# CX4_enable_logic.net
KiCad netlist of a schematic drawn in Altium Designer
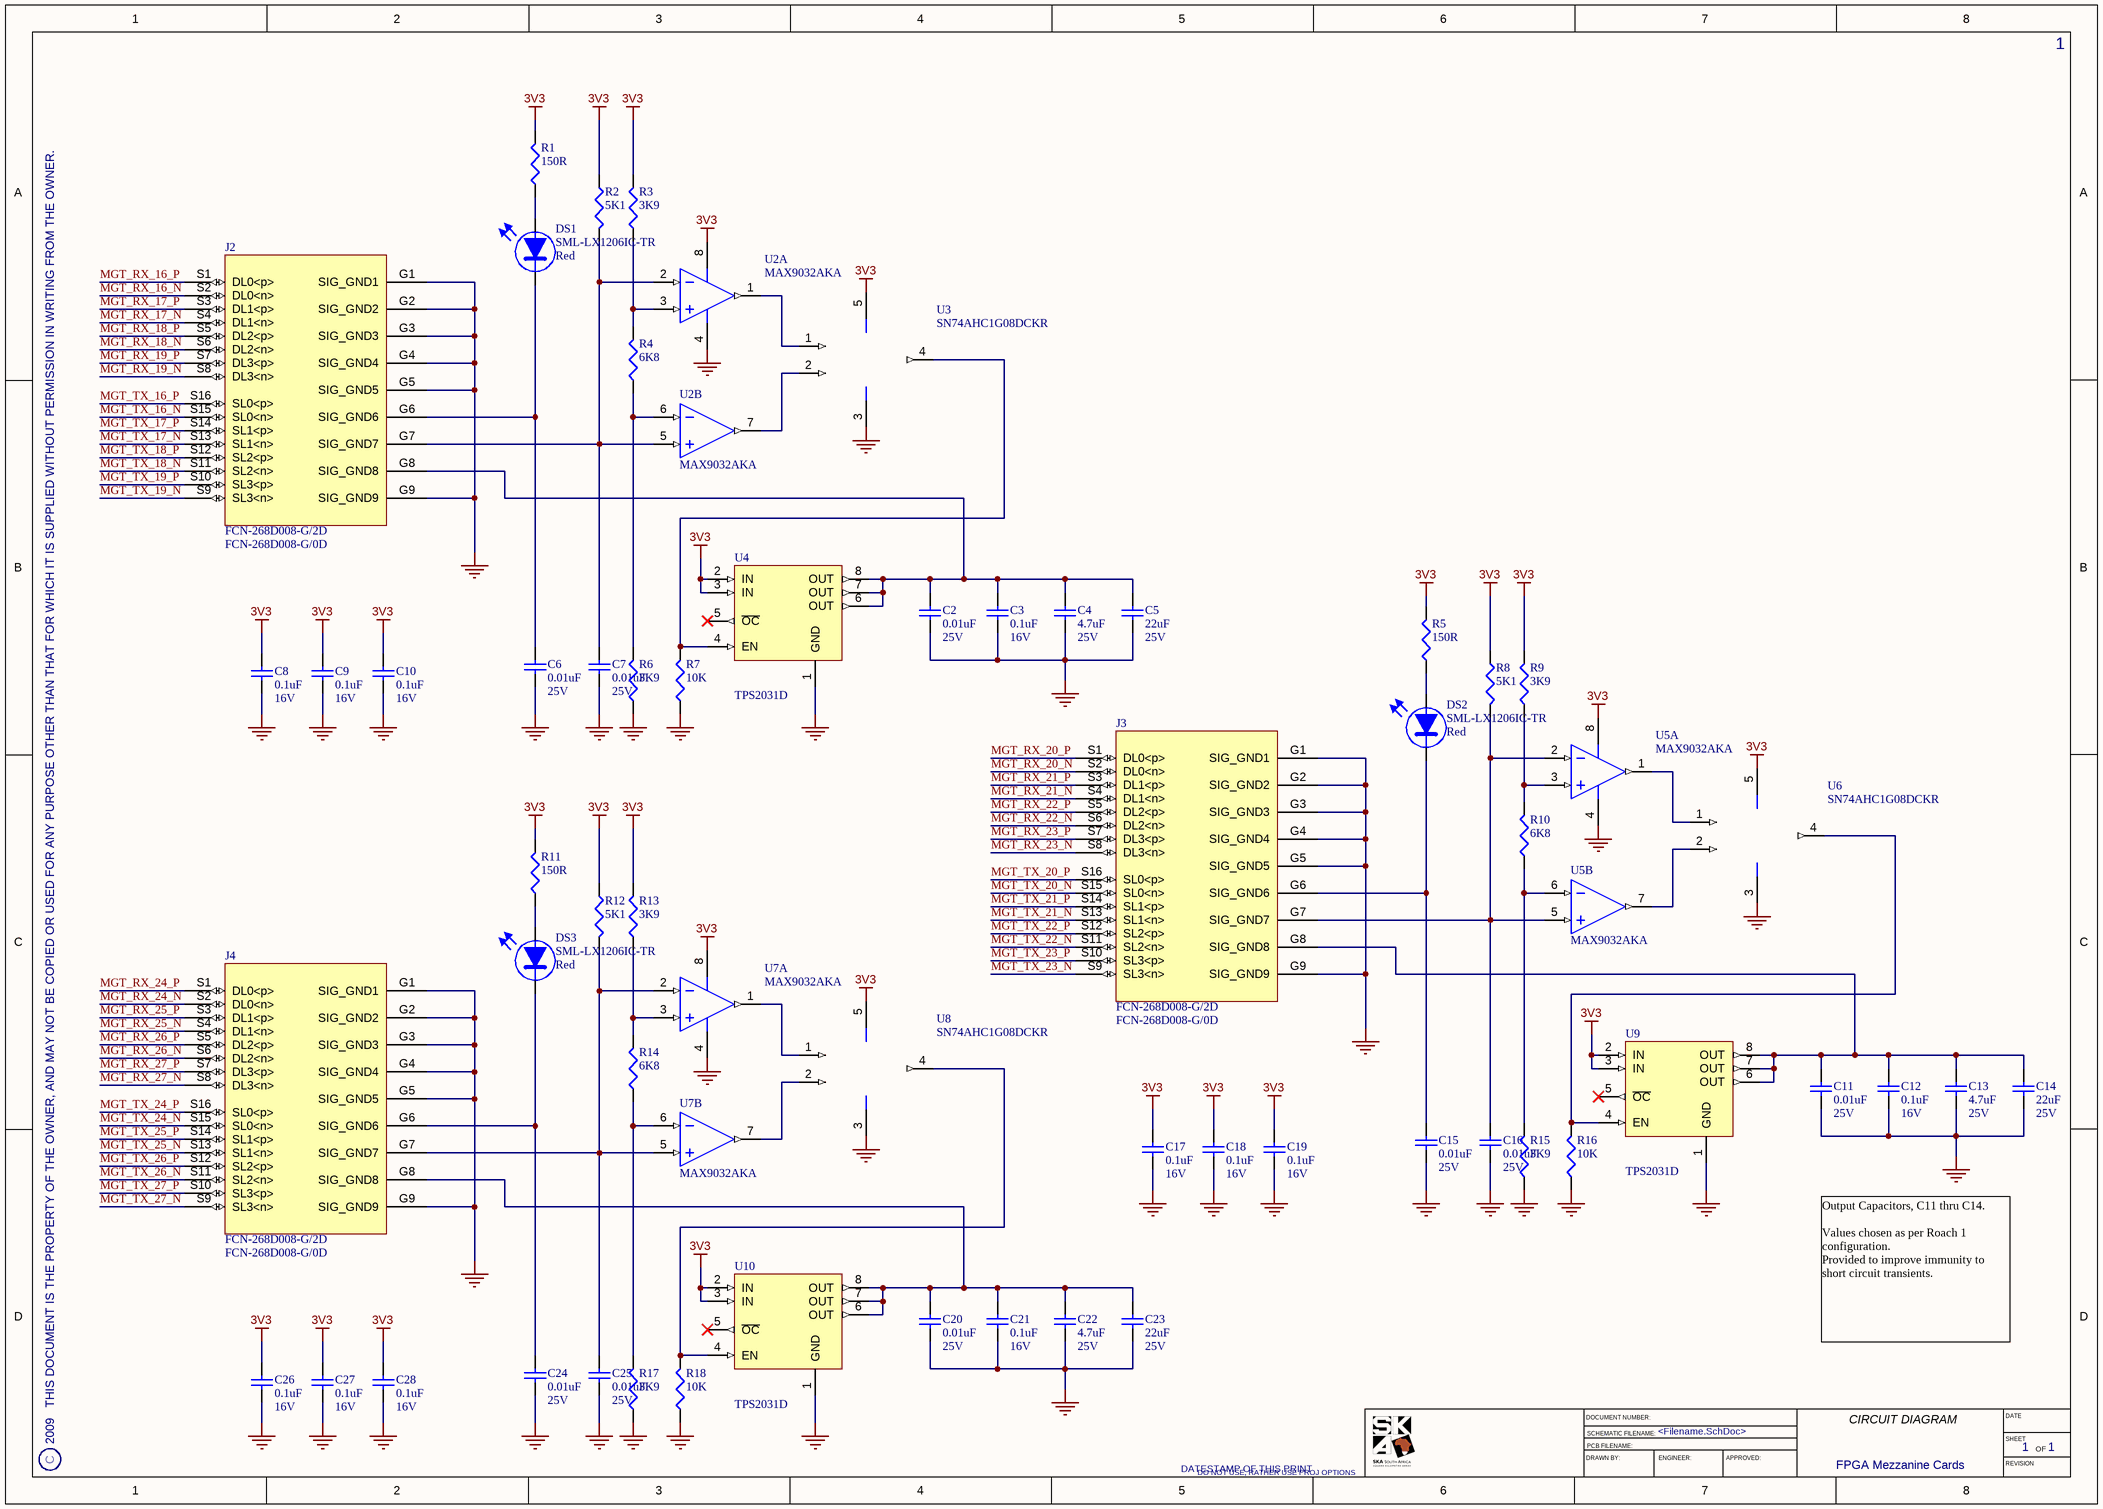
[diagram p0: CX4_enable_logic.SchDoc]

(export (version "E")
  (design (tool "Eeschema 10.0.6"))
  (components
    (comp (ref "C2")
      (value "0.01uF")
      (footprint "CAPC1005X55L")
      (description "0.01uF, Ceramic Capacitor")
      (fields
        (field (name "RATING") "25V")
        (field (name "MANUFACTURER") "MURATA")
        (field (name "PARTNUM") "GRM155R71E103KA01D")
      )
      (libsource (lib "altium_db") (part "CapStd"))
    )
    (comp (ref "C3")
      (value "0.1uF")
      (footprint "CAPC1005X60L")
      (description "0.1uF, Ceramic Capacitor")
      (fields
        (field (name "RATING") "16V")
        (field (name "MANUFACTURER") "VENKEL")
        (field (name "PARTNUM") "C0402X7R160-104KN")
      )
      (libsource (lib "altium_db") (part "CapStd"))
    )
    (comp (ref "C4")
      (value "4.7uF")
      (footprint "CAPC2012X127L")
      (description "4.7uF, Ceramic Capacitor")
      (fields
        (field (name "RATING") "25V")
        (field (name "MANUFACTURER") "MURATA")
        (field (name "PARTNUM") "GRM21BR61E475KA12K")
      )
      (libsource (lib "altium_db") (part "CapStd"))
    )
    (comp (ref "C5")
      (value "22uF")
      (footprint "CAPC3225X270L")
      (description "22uF, Ceramic Capacitor")
      (fields
        (field (name "RATING") "25V")
        (field (name "MANUFACTURER") "MURATA")
        (field (name "PARTNUM") "GRM32ER61E226ME15L")
      )
      (libsource (lib "altium_db") (part "CapStd"))
    )
    (comp (ref "C6")
      (value "0.01uF")
      (footprint "CAPC1005X55L")
      (description "0.01uF, Ceramic Capacitor")
      (fields
        (field (name "RATING") "25V")
        (field (name "MANUFACTURER") "MURATA")
        (field (name "PARTNUM") "GRM155R71E103KA01D")
      )
      (libsource (lib "altium_db") (part "CapStd"))
    )
    (comp (ref "C7")
      (value "0.01uF")
      (footprint "CAPC1005X55L")
      (description "0.01uF, Ceramic Capacitor")
      (fields
        (field (name "RATING") "25V")
        (field (name "MANUFACTURER") "MURATA")
        (field (name "PARTNUM") "GRM155R71E103KA01D")
      )
      (libsource (lib "altium_db") (part "CapStd"))
    )
    (comp (ref "C8")
      (value "0.1uF")
      (footprint "CAPC1005X60L")
      (description "0.1uF, Ceramic Capacitor")
      (fields
        (field (name "RATING") "16V")
        (field (name "MANUFACTURER") "VENKEL")
        (field (name "PARTNUM") "C0402X7R160-104KN")
      )
      (libsource (lib "altium_db") (part "CapStd"))
    )
    (comp (ref "C9")
      (value "0.1uF")
      (footprint "CAPC1005X60L")
      (description "0.1uF, Ceramic Capacitor")
      (fields
        (field (name "RATING") "16V")
        (field (name "MANUFACTURER") "VENKEL")
        (field (name "PARTNUM") "C0402X7R160-104KN")
      )
      (libsource (lib "altium_db") (part "CapStd"))
    )
    (comp (ref "C10")
      (value "0.1uF")
      (footprint "CAPC1005X60L")
      (description "0.1uF, Ceramic Capacitor")
      (fields
        (field (name "RATING") "16V")
        (field (name "MANUFACTURER") "VENKEL")
        (field (name "PARTNUM") "C0402X7R160-104KN")
      )
      (libsource (lib "altium_db") (part "CapStd"))
    )
    (comp (ref "C11")
      (value "0.01uF")
      (footprint "CAPC1005X55L")
      (description "0.01uF, Ceramic Capacitor")
      (fields
        (field (name "RATING") "25V")
        (field (name "MANUFACTURER") "MURATA")
        (field (name "PARTNUM") "GRM155R71E103KA01D")
      )
      (libsource (lib "altium_db") (part "CapStd"))
    )
    (comp (ref "C12")
      (value "0.1uF")
      (footprint "CAPC1005X60L")
      (description "0.1uF, Ceramic Capacitor")
      (fields
        (field (name "RATING") "16V")
        (field (name "MANUFACTURER") "VENKEL")
        (field (name "PARTNUM") "C0402X7R160-104KN")
      )
      (libsource (lib "altium_db") (part "CapStd"))
    )
    (comp (ref "C13")
      (value "4.7uF")
      (footprint "CAPC2012X127L")
      (description "4.7uF, Ceramic Capacitor")
      (fields
        (field (name "RATING") "25V")
        (field (name "MANUFACTURER") "MURATA")
        (field (name "PARTNUM") "GRM21BR61E475KA12K")
      )
      (libsource (lib "altium_db") (part "CapStd"))
    )
    (comp (ref "C14")
      (value "22uF")
      (footprint "CAPC3225X270L")
      (description "22uF, Ceramic Capacitor")
      (fields
        (field (name "RATING") "25V")
        (field (name "MANUFACTURER") "MURATA")
        (field (name "PARTNUM") "GRM32ER61E226ME15L")
      )
      (libsource (lib "altium_db") (part "CapStd"))
    )
    (comp (ref "C15")
      (value "0.01uF")
      (footprint "CAPC1005X55L")
      (description "0.01uF, Ceramic Capacitor")
      (fields
        (field (name "RATING") "25V")
        (field (name "MANUFACTURER") "MURATA")
        (field (name "PARTNUM") "GRM155R71E103KA01D")
      )
      (libsource (lib "altium_db") (part "CapStd"))
    )
    (comp (ref "C16")
      (value "0.01uF")
      (footprint "CAPC1005X55L")
      (description "0.01uF, Ceramic Capacitor")
      (fields
        (field (name "RATING") "25V")
        (field (name "MANUFACTURER") "MURATA")
        (field (name "PARTNUM") "GRM155R71E103KA01D")
      )
      (libsource (lib "altium_db") (part "CapStd"))
    )
    (comp (ref "C17")
      (value "0.1uF")
      (footprint "CAPC1005X60L")
      (description "0.1uF, Ceramic Capacitor")
      (fields
        (field (name "RATING") "16V")
        (field (name "MANUFACTURER") "VENKEL")
        (field (name "PARTNUM") "C0402X7R160-104KN")
      )
      (libsource (lib "altium_db") (part "CapStd"))
    )
    (comp (ref "C18")
      (value "0.1uF")
      (footprint "CAPC1005X60L")
      (description "0.1uF, Ceramic Capacitor")
      (fields
        (field (name "RATING") "16V")
        (field (name "MANUFACTURER") "VENKEL")
        (field (name "PARTNUM") "C0402X7R160-104KN")
      )
      (libsource (lib "altium_db") (part "CapStd"))
    )
    (comp (ref "C19")
      (value "0.1uF")
      (footprint "CAPC1005X60L")
      (description "0.1uF, Ceramic Capacitor")
      (fields
        (field (name "RATING") "16V")
        (field (name "MANUFACTURER") "VENKEL")
        (field (name "PARTNUM") "C0402X7R160-104KN")
      )
      (libsource (lib "altium_db") (part "CapStd"))
    )
    (comp (ref "C20")
      (value "0.01uF")
      (footprint "CAPC1005X55L")
      (description "0.01uF, Ceramic Capacitor")
      (fields
        (field (name "RATING") "25V")
        (field (name "MANUFACTURER") "MURATA")
        (field (name "PARTNUM") "GRM155R71E103KA01D")
      )
      (libsource (lib "altium_db") (part "CapStd"))
    )
    (comp (ref "C21")
      (value "0.1uF")
      (footprint "CAPC1005X60L")
      (description "0.1uF, Ceramic Capacitor")
      (fields
        (field (name "RATING") "16V")
        (field (name "MANUFACTURER") "VENKEL")
        (field (name "PARTNUM") "C0402X7R160-104KN")
      )
      (libsource (lib "altium_db") (part "CapStd"))
    )
    (comp (ref "C22")
      (value "4.7uF")
      (footprint "CAPC2012X127L")
      (description "4.7uF, Ceramic Capacitor")
      (fields
        (field (name "RATING") "25V")
        (field (name "MANUFACTURER") "MURATA")
        (field (name "PARTNUM") "GRM21BR61E475KA12K")
      )
      (libsource (lib "altium_db") (part "CapStd"))
    )
    (comp (ref "C23")
      (value "22uF")
      (footprint "CAPC3225X270L")
      (description "22uF, Ceramic Capacitor")
      (fields
        (field (name "RATING") "25V")
        (field (name "MANUFACTURER") "MURATA")
        (field (name "PARTNUM") "GRM32ER61E226ME15L")
      )
      (libsource (lib "altium_db") (part "CapStd"))
    )
    (comp (ref "C24")
      (value "0.01uF")
      (footprint "CAPC1005X55L")
      (description "0.01uF, Ceramic Capacitor")
      (fields
        (field (name "RATING") "25V")
        (field (name "MANUFACTURER") "MURATA")
        (field (name "PARTNUM") "GRM155R71E103KA01D")
      )
      (libsource (lib "altium_db") (part "CapStd"))
    )
    (comp (ref "C25")
      (value "0.01uF")
      (footprint "CAPC1005X55L")
      (description "0.01uF, Ceramic Capacitor")
      (fields
        (field (name "RATING") "25V")
        (field (name "MANUFACTURER") "MURATA")
        (field (name "PARTNUM") "GRM155R71E103KA01D")
      )
      (libsource (lib "altium_db") (part "CapStd"))
    )
    (comp (ref "C26")
      (value "0.1uF")
      (footprint "CAPC1005X60L")
      (description "0.1uF, Ceramic Capacitor")
      (fields
        (field (name "RATING") "16V")
        (field (name "MANUFACTURER") "VENKEL")
        (field (name "PARTNUM") "C0402X7R160-104KN")
      )
      (libsource (lib "altium_db") (part "CapStd"))
    )
    (comp (ref "C27")
      (value "0.1uF")
      (footprint "CAPC1005X60L")
      (description "0.1uF, Ceramic Capacitor")
      (fields
        (field (name "RATING") "16V")
        (field (name "MANUFACTURER") "VENKEL")
        (field (name "PARTNUM") "C0402X7R160-104KN")
      )
      (libsource (lib "altium_db") (part "CapStd"))
    )
    (comp (ref "C28")
      (value "0.1uF")
      (footprint "CAPC1005X60L")
      (description "0.1uF, Ceramic Capacitor")
      (fields
        (field (name "RATING") "16V")
        (field (name "MANUFACTURER") "VENKEL")
        (field (name "PARTNUM") "C0402X7R160-104KN")
      )
      (libsource (lib "altium_db") (part "CapStd"))
    )
    (comp (ref "DS1")
      (value "SML-LX1206IC-TR")
      (footprint "LEDC3216X120N")
      (description "Red, Surface mount, LED, 1206")
      (fields (field (name "COLOUR") "Red") (field (name "MANUFACTURER") "LUMEX"))
      (libsource (lib "altium_db") (part "LEDSTD"))
    )
    (comp (ref "DS2")
      (value "SML-LX1206IC-TR")
      (footprint "LEDC3216X120N")
      (description "Red, Surface mount, LED, 1206")
      (fields (field (name "COLOUR") "Red") (field (name "MANUFACTURER") "LUMEX"))
      (libsource (lib "altium_db") (part "LEDSTD"))
    )
    (comp (ref "DS3")
      (value "SML-LX1206IC-TR")
      (footprint "LEDC3216X120N")
      (description "Red, Surface mount, LED, 1206")
      (fields (field (name "COLOUR") "Red") (field (name "MANUFACTURER") "LUMEX"))
      (libsource (lib "altium_db") (part "LEDSTD"))
    )
    (comp (ref "J2")
      (value "FCN-268D008-G/2D")
      (footprint "FCN-268D008-G")
      (description "CX4/Infiniband 4 channel Socket Connector")
      (fields (field (name "PARTNUM") "FCN-268D008-G/0D") (field (name "MANUFACTURER") "Fujitsu"))
      (libsource (lib "altium_db") (part "FCN-268D008-G_2"))
    )
    (comp (ref "J3")
      (value "FCN-268D008-G/2D")
      (footprint "FCN-268D008-G")
      (description "CX4/Infiniband 4 channel Socket Connector")
      (fields (field (name "PARTNUM") "FCN-268D008-G/0D") (field (name "MANUFACTURER") "Fujitsu"))
      (libsource (lib "altium_db") (part "FCN-268D008-G_2"))
    )
    (comp (ref "J4")
      (value "FCN-268D008-G/2D")
      (footprint "FCN-268D008-G")
      (description "CX4/Infiniband 4 channel Socket Connector")
      (fields (field (name "PARTNUM") "FCN-268D008-G/0D") (field (name "MANUFACTURER") "Fujitsu"))
      (libsource (lib "altium_db") (part "FCN-268D008-G_2"))
    )
    (comp (ref "R1")
      (value "150R")
      (footprint "RESC1005X40L")
      (description "150R, 1.1mm x 0.5mm, Thick Film Resistor")
      (fields (field (name "MANUFACTURER") "ROYALOHM") (field (name "PARTNUM") "0402WGJ0151T1E"))
      (libsource (lib "altium_db") (part "ResStd"))
    )
    (comp (ref "R2")
      (value "5K1")
      (footprint "RESC1005X40L")
      (description "5K1, 1.1mm x 0.5mm, Thick Film Resistor")
      (fields (field (name "MANUFACTURER") "ROYALOHM") (field (name "PARTNUM") "0402WAJ0512T1E"))
      (libsource (lib "altium_db") (part "ResStd"))
    )
    (comp (ref "R3")
      (value "3K9")
      (footprint "RESC1005X40L")
      (description "3K9, 1.1mm x 0.5mm, Thick Film Resistor")
      (fields (field (name "MANUFACTURER") "ROYALOHM") (field (name "PARTNUM") "0402WGJ0392T1E"))
      (libsource (lib "altium_db") (part "ResStd"))
    )
    (comp (ref "R4")
      (value "6K8")
      (footprint "RESC1005X40L")
      (description "6K8, 1.1mm x 0.5mm, Thick Film Resistor")
      (fields (field (name "MANUFACTURER") "ROYALOHM") (field (name "PARTNUM") "0402WGJ0682T1E"))
      (libsource (lib "altium_db") (part "ResStd"))
    )
    (comp (ref "R5")
      (value "150R")
      (footprint "RESC1005X40L")
      (description "150R, 1.1mm x 0.5mm, Thick Film Resistor")
      (fields (field (name "MANUFACTURER") "ROYALOHM") (field (name "PARTNUM") "0402WGJ0151T1E"))
      (libsource (lib "altium_db") (part "ResStd"))
    )
    (comp (ref "R6")
      (value "3K9")
      (footprint "RESC1005X40L")
      (description "3K9, 1.1mm x 0.5mm, Thick Film Resistor")
      (fields (field (name "MANUFACTURER") "ROYALOHM") (field (name "PARTNUM") "0402WGJ0392T1E"))
      (libsource (lib "altium_db") (part "ResStd"))
    )
    (comp (ref "R7")
      (value "10K")
      (footprint "RESC1005X40L")
      (description "10K, 1.1mm x 0.5mm, Thick Film Resistor")
      (fields (field (name "MANUFACTURER") "ROYALOHM") (field (name "PARTNUM") "0402WGJ0103T1E"))
      (libsource (lib "altium_db") (part "ResStd"))
    )
    (comp (ref "R8")
      (value "5K1")
      (footprint "RESC1005X40L")
      (description "5K1, 1.1mm x 0.5mm, Thick Film Resistor")
      (fields (field (name "MANUFACTURER") "ROYALOHM") (field (name "PARTNUM") "0402WAJ0512T1E"))
      (libsource (lib "altium_db") (part "ResStd"))
    )
    (comp (ref "R9")
      (value "3K9")
      (footprint "RESC1005X40L")
      (description "3K9, 1.1mm x 0.5mm, Thick Film Resistor")
      (fields (field (name "MANUFACTURER") "ROYALOHM") (field (name "PARTNUM") "0402WGJ0392T1E"))
      (libsource (lib "altium_db") (part "ResStd"))
    )
    (comp (ref "R10")
      (value "6K8")
      (footprint "RESC1005X40L")
      (description "6K8, 1.1mm x 0.5mm, Thick Film Resistor")
      (fields (field (name "MANUFACTURER") "ROYALOHM") (field (name "PARTNUM") "0402WGJ0682T1E"))
      (libsource (lib "altium_db") (part "ResStd"))
    )
    (comp (ref "R11")
      (value "150R")
      (footprint "RESC1005X40L")
      (description "150R, 1.1mm x 0.5mm, Thick Film Resistor")
      (fields (field (name "MANUFACTURER") "ROYALOHM") (field (name "PARTNUM") "0402WGJ0151T1E"))
      (libsource (lib "altium_db") (part "ResStd"))
    )
    (comp (ref "R12")
      (value "5K1")
      (footprint "RESC1005X40L")
      (description "5K1, 1.1mm x 0.5mm, Thick Film Resistor")
      (fields (field (name "MANUFACTURER") "ROYALOHM") (field (name "PARTNUM") "0402WAJ0512T1E"))
      (libsource (lib "altium_db") (part "ResStd"))
    )
    (comp (ref "R13")
      (value "3K9")
      (footprint "RESC1005X40L")
      (description "3K9, 1.1mm x 0.5mm, Thick Film Resistor")
      (fields (field (name "MANUFACTURER") "ROYALOHM") (field (name "PARTNUM") "0402WGJ0392T1E"))
      (libsource (lib "altium_db") (part "ResStd"))
    )
    (comp (ref "R14")
      (value "6K8")
      (footprint "RESC1005X40L")
      (description "6K8, 1.1mm x 0.5mm, Thick Film Resistor")
      (fields (field (name "MANUFACTURER") "ROYALOHM") (field (name "PARTNUM") "0402WGJ0682T1E"))
      (libsource (lib "altium_db") (part "ResStd"))
    )
    (comp (ref "R15")
      (value "3K9")
      (footprint "RESC1005X40L")
      (description "3K9, 1.1mm x 0.5mm, Thick Film Resistor")
      (fields (field (name "MANUFACTURER") "ROYALOHM") (field (name "PARTNUM") "0402WGJ0392T1E"))
      (libsource (lib "altium_db") (part "ResStd"))
    )
    (comp (ref "R16")
      (value "10K")
      (footprint "RESC1005X40L")
      (description "10K, 1.1mm x 0.5mm, Thick Film Resistor")
      (fields (field (name "MANUFACTURER") "ROYALOHM") (field (name "PARTNUM") "0402WGJ0103T1E"))
      (libsource (lib "altium_db") (part "ResStd"))
    )
    (comp (ref "R17")
      (value "3K9")
      (footprint "RESC1005X40L")
      (description "3K9, 1.1mm x 0.5mm, Thick Film Resistor")
      (fields (field (name "MANUFACTURER") "ROYALOHM") (field (name "PARTNUM") "0402WGJ0392T1E"))
      (libsource (lib "altium_db") (part "ResStd"))
    )
    (comp (ref "R18")
      (value "10K")
      (footprint "RESC1005X40L")
      (description "10K, 1.1mm x 0.5mm, Thick Film Resistor")
      (fields (field (name "MANUFACTURER") "ROYALOHM") (field (name "PARTNUM") "0402WGJ0103T1E"))
      (libsource (lib "altium_db") (part "ResStd"))
    )
    (comp (ref "U2")
      (value "MAX9032AKA")
      (footprint "TSOT-23-8")
      (description "Dual Single-Supply Comparator")
      (fields (field (name "MANUFACTURER") "MAXIM"))
      (libsource (lib "altium_db") (part "MAX9032"))
    )
    (comp (ref "U3")
      (value "SN74AHC1G08DCKR")
      (footprint "SC70-5")
      (description "Single 2-Input Positive-AND Gate")
      (fields (field (name "MANUFACTURER") "Texas Instruments"))
      (libsource (lib "altium_db") (part "SN74AHC1G08"))
    )
    (comp (ref "U4")
      (value "TPS2031D")
      (footprint "SOIC150-8_N")
      (description "Power-Distribution Switch")
      (fields (field (name "MANUFACTURER") "Texas Instruments"))
      (libsource (lib "altium_db") (part "TPS2031"))
    )
    (comp (ref "U5")
      (value "MAX9032AKA")
      (footprint "TSOT-23-8")
      (description "Dual Single-Supply Comparator")
      (fields (field (name "MANUFACTURER") "MAXIM"))
      (libsource (lib "altium_db") (part "MAX9032"))
    )
    (comp (ref "U6")
      (value "SN74AHC1G08DCKR")
      (footprint "SC70-5")
      (description "Single 2-Input Positive-AND Gate")
      (fields (field (name "MANUFACTURER") "Texas Instruments"))
      (libsource (lib "altium_db") (part "SN74AHC1G08"))
    )
    (comp (ref "U7")
      (value "MAX9032AKA")
      (footprint "TSOT-23-8")
      (description "Dual Single-Supply Comparator")
      (fields (field (name "MANUFACTURER") "MAXIM"))
      (libsource (lib "altium_db") (part "MAX9032"))
    )
    (comp (ref "U8")
      (value "SN74AHC1G08DCKR")
      (footprint "SC70-5")
      (description "Single 2-Input Positive-AND Gate")
      (fields (field (name "MANUFACTURER") "Texas Instruments"))
      (libsource (lib "altium_db") (part "SN74AHC1G08"))
    )
    (comp (ref "U9")
      (value "TPS2031D")
      (footprint "SOIC150-8_N")
      (description "Power-Distribution Switch")
      (fields (field (name "MANUFACTURER") "Texas Instruments"))
      (libsource (lib "altium_db") (part "TPS2031"))
    )
    (comp (ref "U10")
      (value "TPS2031D")
      (footprint "SOIC150-8_N")
      (description "Power-Distribution Switch")
      (fields (field (name "MANUFACTURER") "Texas Instruments"))
      (libsource (lib "altium_db") (part "TPS2031"))
    )
  )
  (nets
    (net (code "1") (name "/MGT_RX_16_N") (class "Default")
      (node (ref "J2") (pin "S2") (pinfunction "DL0<n>_S2") (pintype "bidirectional"))
    )
    (net (code "2") (name "/MGT_RX_16_P") (class "Default")
      (node (ref "J2") (pin "S1") (pinfunction "DL0<p>_S1") (pintype "bidirectional"))
    )
    (net (code "3") (name "/MGT_RX_17_N") (class "Default")
      (node (ref "J2") (pin "S4") (pinfunction "DL1<n>_S4") (pintype "bidirectional"))
    )
    (net (code "4") (name "/MGT_RX_17_P") (class "Default")
      (node (ref "J2") (pin "S3") (pinfunction "DL1<p>_S3") (pintype "bidirectional"))
    )
    (net (code "5") (name "/MGT_RX_18_N") (class "Default")
      (node (ref "J2") (pin "S6") (pinfunction "DL2<n>_S6") (pintype "bidirectional"))
    )
    (net (code "6") (name "/MGT_RX_18_P") (class "Default")
      (node (ref "J2") (pin "S5") (pinfunction "DL2<p>_S5") (pintype "bidirectional"))
    )
    (net (code "7") (name "/MGT_RX_19_N") (class "Default")
      (node (ref "J2") (pin "S8") (pinfunction "DL3<n>_S8") (pintype "bidirectional"))
    )
    (net (code "8") (name "/MGT_RX_19_P") (class "Default")
      (node (ref "J2") (pin "S7") (pinfunction "DL3<p>_S7") (pintype "bidirectional"))
    )
    (net (code "9") (name "/MGT_RX_20_N") (class "Default")
      (node (ref "J3") (pin "S2") (pinfunction "DL0<n>_S2") (pintype "bidirectional"))
    )
    (net (code "10") (name "/MGT_RX_20_P") (class "Default")
      (node (ref "J3") (pin "S1") (pinfunction "DL0<p>_S1") (pintype "bidirectional"))
    )
    (net (code "11") (name "/MGT_RX_21_N") (class "Default")
      (node (ref "J3") (pin "S4") (pinfunction "DL1<n>_S4") (pintype "bidirectional"))
    )
    (net (code "12") (name "/MGT_RX_21_P") (class "Default")
      (node (ref "J3") (pin "S3") (pinfunction "DL1<p>_S3") (pintype "bidirectional"))
    )
    (net (code "13") (name "/MGT_RX_22_N") (class "Default")
      (node (ref "J3") (pin "S6") (pinfunction "DL2<n>_S6") (pintype "bidirectional"))
    )
    (net (code "14") (name "/MGT_RX_22_P") (class "Default")
      (node (ref "J3") (pin "S5") (pinfunction "DL2<p>_S5") (pintype "bidirectional"))
    )
    (net (code "15") (name "/MGT_RX_23_N") (class "Default")
      (node (ref "J3") (pin "S8") (pinfunction "DL3<n>_S8") (pintype "bidirectional"))
    )
    (net (code "16") (name "/MGT_RX_23_P") (class "Default")
      (node (ref "J3") (pin "S7") (pinfunction "DL3<p>_S7") (pintype "bidirectional"))
    )
    (net (code "17") (name "/MGT_RX_24_N") (class "Default")
      (node (ref "J4") (pin "S2") (pinfunction "DL0<n>_S2") (pintype "bidirectional"))
    )
    (net (code "18") (name "/MGT_RX_24_P") (class "Default")
      (node (ref "J4") (pin "S1") (pinfunction "DL0<p>_S1") (pintype "bidirectional"))
    )
    (net (code "19") (name "/MGT_RX_25_N") (class "Default")
      (node (ref "J4") (pin "S4") (pinfunction "DL1<n>_S4") (pintype "bidirectional"))
    )
    (net (code "20") (name "/MGT_RX_25_P") (class "Default")
      (node (ref "J4") (pin "S3") (pinfunction "DL1<p>_S3") (pintype "bidirectional"))
    )
    (net (code "21") (name "/MGT_RX_26_N") (class "Default")
      (node (ref "J4") (pin "S6") (pinfunction "DL2<n>_S6") (pintype "bidirectional"))
    )
    (net (code "22") (name "/MGT_RX_26_P") (class "Default")
      (node (ref "J4") (pin "S5") (pinfunction "DL2<p>_S5") (pintype "bidirectional"))
    )
    (net (code "23") (name "/MGT_RX_27_N") (class "Default")
      (node (ref "J4") (pin "S8") (pinfunction "DL3<n>_S8") (pintype "bidirectional"))
    )
    (net (code "24") (name "/MGT_RX_27_P") (class "Default")
      (node (ref "J4") (pin "S7") (pinfunction "DL3<p>_S7") (pintype "bidirectional"))
    )
    (net (code "25") (name "/MGT_TX_16_N") (class "Default")
      (node (ref "J2") (pin "S15") (pinfunction "SL0<n>_S15") (pintype "bidirectional"))
    )
    (net (code "26") (name "/MGT_TX_16_P") (class "Default")
      (node (ref "J2") (pin "S16") (pinfunction "SL0<p>_S16") (pintype "bidirectional"))
    )
    (net (code "27") (name "/MGT_TX_17_N") (class "Default")
      (node (ref "J2") (pin "S13") (pinfunction "SL1<n>_S13") (pintype "bidirectional"))
    )
    (net (code "28") (name "/MGT_TX_17_P") (class "Default")
      (node (ref "J2") (pin "S14") (pinfunction "SL1<p>_S14") (pintype "bidirectional"))
    )
    (net (code "29") (name "/MGT_TX_18_N") (class "Default")
      (node (ref "J2") (pin "S11") (pinfunction "SL2<n>_S11") (pintype "bidirectional"))
    )
    (net (code "30") (name "/MGT_TX_18_P") (class "Default")
      (node (ref "J2") (pin "S12") (pinfunction "SL2<p>_S12") (pintype "bidirectional"))
    )
    (net (code "31") (name "/MGT_TX_19_N") (class "Default")
      (node (ref "J2") (pin "S9") (pinfunction "SL3<n>_S9") (pintype "bidirectional"))
    )
    (net (code "32") (name "/MGT_TX_19_P") (class "Default")
      (node (ref "J2") (pin "S10") (pinfunction "SL3<p>_S10") (pintype "bidirectional"))
    )
    (net (code "33") (name "/MGT_TX_20_N") (class "Default")
      (node (ref "J3") (pin "S15") (pinfunction "SL0<n>_S15") (pintype "bidirectional"))
    )
    (net (code "34") (name "/MGT_TX_20_P") (class "Default")
      (node (ref "J3") (pin "S16") (pinfunction "SL0<p>_S16") (pintype "bidirectional"))
    )
    (net (code "35") (name "/MGT_TX_21_N") (class "Default")
      (node (ref "J3") (pin "S13") (pinfunction "SL1<n>_S13") (pintype "bidirectional"))
    )
    (net (code "36") (name "/MGT_TX_21_P") (class "Default")
      (node (ref "J3") (pin "S14") (pinfunction "SL1<p>_S14") (pintype "bidirectional"))
    )
    (net (code "37") (name "/MGT_TX_22_N") (class "Default")
      (node (ref "J3") (pin "S11") (pinfunction "SL2<n>_S11") (pintype "bidirectional"))
    )
    (net (code "38") (name "/MGT_TX_22_P") (class "Default")
      (node (ref "J3") (pin "S12") (pinfunction "SL2<p>_S12") (pintype "bidirectional"))
    )
    (net (code "39") (name "/MGT_TX_23_N") (class "Default")
      (node (ref "J3") (pin "S9") (pinfunction "SL3<n>_S9") (pintype "bidirectional"))
    )
    (net (code "40") (name "/MGT_TX_23_P") (class "Default")
      (node (ref "J3") (pin "S10") (pinfunction "SL3<p>_S10") (pintype "bidirectional"))
    )
    (net (code "41") (name "/MGT_TX_24_N") (class "Default")
      (node (ref "J4") (pin "S15") (pinfunction "SL0<n>_S15") (pintype "bidirectional"))
    )
    (net (code "42") (name "/MGT_TX_24_P") (class "Default")
      (node (ref "J4") (pin "S16") (pinfunction "SL0<p>_S16") (pintype "bidirectional"))
    )
    (net (code "43") (name "/MGT_TX_25_N") (class "Default")
      (node (ref "J4") (pin "S13") (pinfunction "SL1<n>_S13") (pintype "bidirectional"))
    )
    (net (code "44") (name "/MGT_TX_25_P") (class "Default")
      (node (ref "J4") (pin "S14") (pinfunction "SL1<p>_S14") (pintype "bidirectional"))
    )
    (net (code "45") (name "/MGT_TX_26_N") (class "Default")
      (node (ref "J4") (pin "S11") (pinfunction "SL2<n>_S11") (pintype "bidirectional"))
    )
    (net (code "46") (name "/MGT_TX_26_P") (class "Default")
      (node (ref "J4") (pin "S12") (pinfunction "SL2<p>_S12") (pintype "bidirectional"))
    )
    (net (code "47") (name "/MGT_TX_27_N") (class "Default")
      (node (ref "J4") (pin "S9") (pinfunction "SL3<n>_S9") (pintype "bidirectional"))
    )
    (net (code "48") (name "/MGT_TX_27_P") (class "Default")
      (node (ref "J4") (pin "S10") (pinfunction "SL3<p>_S10") (pintype "bidirectional"))
    )
    (net (code "49") (name "3V3") (class "Default")
      (node (ref "C10") (pin "2") (pinfunction "2_2") (pintype "passive"))
      (node (ref "C17") (pin "2") (pinfunction "2_2") (pintype "passive"))
      (node (ref "C18") (pin "2") (pinfunction "2_2") (pintype "passive"))
      (node (ref "C19") (pin "2") (pinfunction "2_2") (pintype "passive"))
      (node (ref "C26") (pin "2") (pinfunction "2_2") (pintype "passive"))
      (node (ref "C27") (pin "2") (pinfunction "2_2") (pintype "passive"))
      (node (ref "C28") (pin "2") (pinfunction "2_2") (pintype "passive"))
      (node (ref "C8") (pin "2") (pinfunction "2_2") (pintype "passive"))
      (node (ref "C9") (pin "2") (pinfunction "2_2") (pintype "passive"))
      (node (ref "R1") (pin "2") (pinfunction "2_2") (pintype "passive"))
      (node (ref "R11") (pin "2") (pinfunction "2_2") (pintype "passive"))
      (node (ref "R12") (pin "1") (pinfunction "1_1") (pintype "passive"))
      (node (ref "R13") (pin "2") (pinfunction "2_2") (pintype "passive"))
      (node (ref "R2") (pin "1") (pinfunction "1_1") (pintype "passive"))
      (node (ref "R3") (pin "2") (pinfunction "2_2") (pintype "passive"))
      (node (ref "R5") (pin "2") (pinfunction "2_2") (pintype "passive"))
      (node (ref "R8") (pin "1") (pinfunction "1_1") (pintype "passive"))
      (node (ref "R9") (pin "2") (pinfunction "2_2") (pintype "passive"))
      (node (ref "U10") (pin "2") (pinfunction "IN_2") (pintype "input"))
      (node (ref "U10") (pin "3") (pinfunction "IN_3") (pintype "input"))
      (node (ref "U2") (pin "8") (pinfunction "V+_8") (pintype "power_in"))
      (node (ref "U3") (pin "5") (pinfunction "Vcc_5") (pintype "power_in"))
      (node (ref "U4") (pin "2") (pinfunction "IN_2") (pintype "input"))
      (node (ref "U4") (pin "3") (pinfunction "IN_3") (pintype "input"))
      (node (ref "U5") (pin "8") (pinfunction "V+_8") (pintype "power_in"))
      (node (ref "U6") (pin "5") (pinfunction "Vcc_5") (pintype "power_in"))
      (node (ref "U7") (pin "8") (pinfunction "V+_8") (pintype "power_in"))
      (node (ref "U8") (pin "5") (pinfunction "Vcc_5") (pintype "power_in"))
      (node (ref "U9") (pin "2") (pinfunction "IN_2") (pintype "input"))
      (node (ref "U9") (pin "3") (pinfunction "IN_3") (pintype "input"))
    )
    (net (code "50") (name "GND") (class "Default")
      (node (ref "C10") (pin "1") (pinfunction "1_1") (pintype "passive"))
      (node (ref "C11") (pin "1") (pinfunction "1_1") (pintype "passive"))
      (node (ref "C12") (pin "1") (pinfunction "1_1") (pintype "passive"))
      (node (ref "C13") (pin "1") (pinfunction "1_1") (pintype "passive"))
      (node (ref "C14") (pin "1") (pinfunction "1_1") (pintype "passive"))
      (node (ref "C15") (pin "1") (pinfunction "1_1") (pintype "passive"))
      (node (ref "C16") (pin "1") (pinfunction "1_1") (pintype "passive"))
      (node (ref "C17") (pin "1") (pinfunction "1_1") (pintype "passive"))
      (node (ref "C18") (pin "1") (pinfunction "1_1") (pintype "passive"))
      (node (ref "C19") (pin "1") (pinfunction "1_1") (pintype "passive"))
      (node (ref "C2") (pin "1") (pinfunction "1_1") (pintype "passive"))
      (node (ref "C20") (pin "1") (pinfunction "1_1") (pintype "passive"))
      (node (ref "C21") (pin "1") (pinfunction "1_1") (pintype "passive"))
      (node (ref "C22") (pin "1") (pinfunction "1_1") (pintype "passive"))
      (node (ref "C23") (pin "1") (pinfunction "1_1") (pintype "passive"))
      (node (ref "C24") (pin "1") (pinfunction "1_1") (pintype "passive"))
      (node (ref "C25") (pin "1") (pinfunction "1_1") (pintype "passive"))
      (node (ref "C26") (pin "1") (pinfunction "1_1") (pintype "passive"))
      (node (ref "C27") (pin "1") (pinfunction "1_1") (pintype "passive"))
      (node (ref "C28") (pin "1") (pinfunction "1_1") (pintype "passive"))
      (node (ref "C3") (pin "1") (pinfunction "1_1") (pintype "passive"))
      (node (ref "C4") (pin "1") (pinfunction "1_1") (pintype "passive"))
      (node (ref "C5") (pin "1") (pinfunction "1_1") (pintype "passive"))
      (node (ref "C6") (pin "1") (pinfunction "1_1") (pintype "passive"))
      (node (ref "C7") (pin "1") (pinfunction "1_1") (pintype "passive"))
      (node (ref "C8") (pin "1") (pinfunction "1_1") (pintype "passive"))
      (node (ref "C9") (pin "1") (pinfunction "1_1") (pintype "passive"))
      (node (ref "J2") (pin "G1") (pinfunction "SIG_GND1_G1") (pintype "power_in"))
      (node (ref "J2") (pin "G2") (pinfunction "SIG_GND2_G2") (pintype "power_in"))
      (node (ref "J2") (pin "G3") (pinfunction "SIG_GND3_G3") (pintype "power_in"))
      (node (ref "J2") (pin "G4") (pinfunction "SIG_GND4_G4") (pintype "power_in"))
      (node (ref "J2") (pin "G5") (pinfunction "SIG_GND5_G5") (pintype "power_in"))
      (node (ref "J2") (pin "G9") (pinfunction "SIG_GND9_G9") (pintype "power_in"))
      (node (ref "J3") (pin "G1") (pinfunction "SIG_GND1_G1") (pintype "power_in"))
      (node (ref "J3") (pin "G2") (pinfunction "SIG_GND2_G2") (pintype "power_in"))
      (node (ref "J3") (pin "G3") (pinfunction "SIG_GND3_G3") (pintype "power_in"))
      (node (ref "J3") (pin "G4") (pinfunction "SIG_GND4_G4") (pintype "power_in"))
      (node (ref "J3") (pin "G5") (pinfunction "SIG_GND5_G5") (pintype "power_in"))
      (node (ref "J3") (pin "G9") (pinfunction "SIG_GND9_G9") (pintype "power_in"))
      (node (ref "J4") (pin "G1") (pinfunction "SIG_GND1_G1") (pintype "power_in"))
      (node (ref "J4") (pin "G2") (pinfunction "SIG_GND2_G2") (pintype "power_in"))
      (node (ref "J4") (pin "G3") (pinfunction "SIG_GND3_G3") (pintype "power_in"))
      (node (ref "J4") (pin "G4") (pinfunction "SIG_GND4_G4") (pintype "power_in"))
      (node (ref "J4") (pin "G5") (pinfunction "SIG_GND5_G5") (pintype "power_in"))
      (node (ref "J4") (pin "G9") (pinfunction "SIG_GND9_G9") (pintype "power_in"))
      (node (ref "R15") (pin "1") (pinfunction "1_1") (pintype "passive"))
      (node (ref "R16") (pin "1") (pinfunction "1_1") (pintype "passive"))
      (node (ref "R17") (pin "1") (pinfunction "1_1") (pintype "passive"))
      (node (ref "R18") (pin "1") (pinfunction "1_1") (pintype "passive"))
      (node (ref "R6") (pin "1") (pinfunction "1_1") (pintype "passive"))
      (node (ref "R7") (pin "1") (pinfunction "1_1") (pintype "passive"))
      (node (ref "U10") (pin "1") (pinfunction "GND_1") (pintype "power_in"))
      (node (ref "U2") (pin "4") (pinfunction "V-_4") (pintype "power_in"))
      (node (ref "U3") (pin "3") (pinfunction "GND_3") (pintype "power_in"))
      (node (ref "U4") (pin "1") (pinfunction "GND_1") (pintype "power_in"))
      (node (ref "U5") (pin "4") (pinfunction "V-_4") (pintype "power_in"))
      (node (ref "U6") (pin "3") (pinfunction "GND_3") (pintype "power_in"))
      (node (ref "U7") (pin "4") (pinfunction "V-_4") (pintype "power_in"))
      (node (ref "U8") (pin "3") (pinfunction "GND_3") (pintype "power_in"))
      (node (ref "U9") (pin "1") (pinfunction "GND_1") (pintype "power_in"))
    )
    (net (code "51") (name "Net-(DS1-A)") (class "Default")
      (node (ref "DS1") (pin "2") (pinfunction "A_2") (pintype "passive"))
      (node (ref "R1") (pin "1") (pinfunction "1_1") (pintype "passive"))
    )
    (net (code "52") (name "Net-(DS1-K)") (class "Default")
      (node (ref "C6") (pin "2") (pinfunction "2_2") (pintype "passive"))
      (node (ref "DS1") (pin "1") (pinfunction "K_1") (pintype "passive"))
      (node (ref "J2") (pin "G6") (pinfunction "SIG_GND6_G6") (pintype "power_in"))
    )
    (net (code "53") (name "Net-(DS2-A)") (class "Default")
      (node (ref "DS2") (pin "2") (pinfunction "A_2") (pintype "passive"))
      (node (ref "R5") (pin "1") (pinfunction "1_1") (pintype "passive"))
    )
    (net (code "54") (name "Net-(DS2-K)") (class "Default")
      (node (ref "C15") (pin "2") (pinfunction "2_2") (pintype "passive"))
      (node (ref "DS2") (pin "1") (pinfunction "K_1") (pintype "passive"))
      (node (ref "J3") (pin "G6") (pinfunction "SIG_GND6_G6") (pintype "power_in"))
    )
    (net (code "55") (name "Net-(DS3-A)") (class "Default")
      (node (ref "DS3") (pin "2") (pinfunction "A_2") (pintype "passive"))
      (node (ref "R11") (pin "1") (pinfunction "1_1") (pintype "passive"))
    )
    (net (code "56") (name "Net-(DS3-K)") (class "Default")
      (node (ref "C24") (pin "2") (pinfunction "2_2") (pintype "passive"))
      (node (ref "DS3") (pin "1") (pinfunction "K_1") (pintype "passive"))
      (node (ref "J4") (pin "G6") (pinfunction "SIG_GND6_G6") (pintype "power_in"))
    )
    (net (code "57") (name "Net-(J2-SIG_GND7)") (class "Default")
      (node (ref "C7") (pin "2") (pinfunction "2_2") (pintype "passive"))
      (node (ref "J2") (pin "G7") (pinfunction "SIG_GND7_G7") (pintype "power_in"))
      (node (ref "R2") (pin "2") (pinfunction "2_2") (pintype "passive"))
      (node (ref "U2") (pin "2") (pinfunction "INA-_2") (pintype "input"))
      (node (ref "U2") (pin "5") (pinfunction "INB+_5") (pintype "input"))
    )
    (net (code "58") (name "Net-(J2-SIG_GND8)") (class "Default")
      (node (ref "C2") (pin "2") (pinfunction "2_2") (pintype "passive"))
      (node (ref "C3") (pin "2") (pinfunction "2_2") (pintype "passive"))
      (node (ref "C4") (pin "2") (pinfunction "2_2") (pintype "passive"))
      (node (ref "C5") (pin "2") (pinfunction "2_2") (pintype "passive"))
      (node (ref "J2") (pin "G8") (pinfunction "SIG_GND8_G8") (pintype "power_in"))
      (node (ref "U4") (pin "6") (pinfunction "OUT_6") (pintype "output"))
      (node (ref "U4") (pin "7") (pinfunction "OUT_7") (pintype "output"))
      (node (ref "U4") (pin "8") (pinfunction "OUT_8") (pintype "output"))
    )
    (net (code "59") (name "Net-(J3-SIG_GND7)") (class "Default")
      (node (ref "C16") (pin "2") (pinfunction "2_2") (pintype "passive"))
      (node (ref "J3") (pin "G7") (pinfunction "SIG_GND7_G7") (pintype "power_in"))
      (node (ref "R8") (pin "2") (pinfunction "2_2") (pintype "passive"))
      (node (ref "U5") (pin "2") (pinfunction "INA-_2") (pintype "input"))
      (node (ref "U5") (pin "5") (pinfunction "INB+_5") (pintype "input"))
    )
    (net (code "60") (name "Net-(J3-SIG_GND8)") (class "Default")
      (node (ref "C11") (pin "2") (pinfunction "2_2") (pintype "passive"))
      (node (ref "C12") (pin "2") (pinfunction "2_2") (pintype "passive"))
      (node (ref "C13") (pin "2") (pinfunction "2_2") (pintype "passive"))
      (node (ref "C14") (pin "2") (pinfunction "2_2") (pintype "passive"))
      (node (ref "J3") (pin "G8") (pinfunction "SIG_GND8_G8") (pintype "power_in"))
      (node (ref "U9") (pin "6") (pinfunction "OUT_6") (pintype "output"))
      (node (ref "U9") (pin "7") (pinfunction "OUT_7") (pintype "output"))
      (node (ref "U9") (pin "8") (pinfunction "OUT_8") (pintype "output"))
    )
    (net (code "61") (name "Net-(J4-SIG_GND7)") (class "Default")
      (node (ref "C25") (pin "2") (pinfunction "2_2") (pintype "passive"))
      (node (ref "J4") (pin "G7") (pinfunction "SIG_GND7_G7") (pintype "power_in"))
      (node (ref "R12") (pin "2") (pinfunction "2_2") (pintype "passive"))
      (node (ref "U7") (pin "2") (pinfunction "INA-_2") (pintype "input"))
      (node (ref "U7") (pin "5") (pinfunction "INB+_5") (pintype "input"))
    )
    (net (code "62") (name "Net-(J4-SIG_GND8)") (class "Default")
      (node (ref "C20") (pin "2") (pinfunction "2_2") (pintype "passive"))
      (node (ref "C21") (pin "2") (pinfunction "2_2") (pintype "passive"))
      (node (ref "C22") (pin "2") (pinfunction "2_2") (pintype "passive"))
      (node (ref "C23") (pin "2") (pinfunction "2_2") (pintype "passive"))
      (node (ref "J4") (pin "G8") (pinfunction "SIG_GND8_G8") (pintype "power_in"))
      (node (ref "U10") (pin "6") (pinfunction "OUT_6") (pintype "output"))
      (node (ref "U10") (pin "7") (pinfunction "OUT_7") (pintype "output"))
      (node (ref "U10") (pin "8") (pinfunction "OUT_8") (pintype "output"))
    )
    (net (code "63") (name "Net-(U2A-INA+)") (class "Default")
      (node (ref "R3") (pin "1") (pinfunction "1_1") (pintype "passive"))
      (node (ref "R4") (pin "2") (pinfunction "2_2") (pintype "passive"))
      (node (ref "U2") (pin "3") (pinfunction "INA+_3") (pintype "input"))
    )
    (net (code "64") (name "Net-(U2A-OUTA)") (class "Default")
      (node (ref "U2") (pin "1") (pinfunction "OUTA_1") (pintype "output"))
      (node (ref "U3") (pin "1") (pinfunction "IN_(A)_1") (pintype "input"))
    )
    (net (code "65") (name "Net-(U2B-INB-)") (class "Default")
      (node (ref "R4") (pin "1") (pinfunction "1_1") (pintype "passive"))
      (node (ref "R6") (pin "2") (pinfunction "2_2") (pintype "passive"))
      (node (ref "U2") (pin "6") (pinfunction "INB-_6") (pintype "input"))
    )
    (net (code "66") (name "Net-(U2B-OUTB)") (class "Default")
      (node (ref "U2") (pin "7") (pinfunction "OUTB_7") (pintype "output"))
      (node (ref "U3") (pin "2") (pinfunction "IN_(B)_2") (pintype "input"))
    )
    (net (code "67") (name "Net-(U3-OUT_(Y))") (class "Default")
      (node (ref "R7") (pin "2") (pinfunction "2_2") (pintype "passive"))
      (node (ref "U3") (pin "4") (pinfunction "OUT_(Y)_4") (pintype "output"))
      (node (ref "U4") (pin "4") (pinfunction "EN_4") (pintype "input"))
    )
    (net (code "68") (name "Net-(U5A-INA+)") (class "Default")
      (node (ref "R10") (pin "2") (pinfunction "2_2") (pintype "passive"))
      (node (ref "R9") (pin "1") (pinfunction "1_1") (pintype "passive"))
      (node (ref "U5") (pin "3") (pinfunction "INA+_3") (pintype "input"))
    )
    (net (code "69") (name "Net-(U5A-OUTA)") (class "Default")
      (node (ref "U5") (pin "1") (pinfunction "OUTA_1") (pintype "output"))
      (node (ref "U6") (pin "1") (pinfunction "IN_(A)_1") (pintype "input"))
    )
    (net (code "70") (name "Net-(U5B-INB-)") (class "Default")
      (node (ref "R10") (pin "1") (pinfunction "1_1") (pintype "passive"))
      (node (ref "R15") (pin "2") (pinfunction "2_2") (pintype "passive"))
      (node (ref "U5") (pin "6") (pinfunction "INB-_6") (pintype "input"))
    )
    (net (code "71") (name "Net-(U5B-OUTB)") (class "Default")
      (node (ref "U5") (pin "7") (pinfunction "OUTB_7") (pintype "output"))
      (node (ref "U6") (pin "2") (pinfunction "IN_(B)_2") (pintype "input"))
    )
    (net (code "72") (name "Net-(U6-OUT_(Y))") (class "Default")
      (node (ref "R16") (pin "2") (pinfunction "2_2") (pintype "passive"))
      (node (ref "U6") (pin "4") (pinfunction "OUT_(Y)_4") (pintype "output"))
      (node (ref "U9") (pin "4") (pinfunction "EN_4") (pintype "input"))
    )
    (net (code "73") (name "Net-(U7A-INA+)") (class "Default")
      (node (ref "R13") (pin "1") (pinfunction "1_1") (pintype "passive"))
      (node (ref "R14") (pin "2") (pinfunction "2_2") (pintype "passive"))
      (node (ref "U7") (pin "3") (pinfunction "INA+_3") (pintype "input"))
    )
    (net (code "74") (name "Net-(U7A-OUTA)") (class "Default")
      (node (ref "U7") (pin "1") (pinfunction "OUTA_1") (pintype "output"))
      (node (ref "U8") (pin "1") (pinfunction "IN_(A)_1") (pintype "input"))
    )
    (net (code "75") (name "Net-(U7B-INB-)") (class "Default")
      (node (ref "R14") (pin "1") (pinfunction "1_1") (pintype "passive"))
      (node (ref "R17") (pin "2") (pinfunction "2_2") (pintype "passive"))
      (node (ref "U7") (pin "6") (pinfunction "INB-_6") (pintype "input"))
    )
    (net (code "76") (name "Net-(U7B-OUTB)") (class "Default")
      (node (ref "U7") (pin "7") (pinfunction "OUTB_7") (pintype "output"))
      (node (ref "U8") (pin "2") (pinfunction "IN_(B)_2") (pintype "input"))
    )
    (net (code "77") (name "Net-(U10-EN)") (class "Default")
      (node (ref "R18") (pin "2") (pinfunction "2_2") (pintype "passive"))
      (node (ref "U10") (pin "4") (pinfunction "EN_4") (pintype "input"))
      (node (ref "U8") (pin "4") (pinfunction "OUT_(Y)_4") (pintype "output"))
    )
    (net (code "78") (name "unconnected-(U4-~{OC}-Pad5)") (class "Default")
      (node (ref "U4") (pin "5") (pinfunction "~{OC}_5") (pintype "output+no_connect"))
    )
    (net (code "79") (name "unconnected-(U9-~{OC}-Pad5)") (class "Default")
      (node (ref "U9") (pin "5") (pinfunction "~{OC}_5") (pintype "output+no_connect"))
    )
    (net (code "80") (name "unconnected-(U10-~{OC}-Pad5)") (class "Default")
      (node (ref "U10") (pin "5") (pinfunction "~{OC}_5") (pintype "output+no_connect"))
    )
  )
)
